# Power.net
KiCad netlist of a schematic drawn in Altium Designer
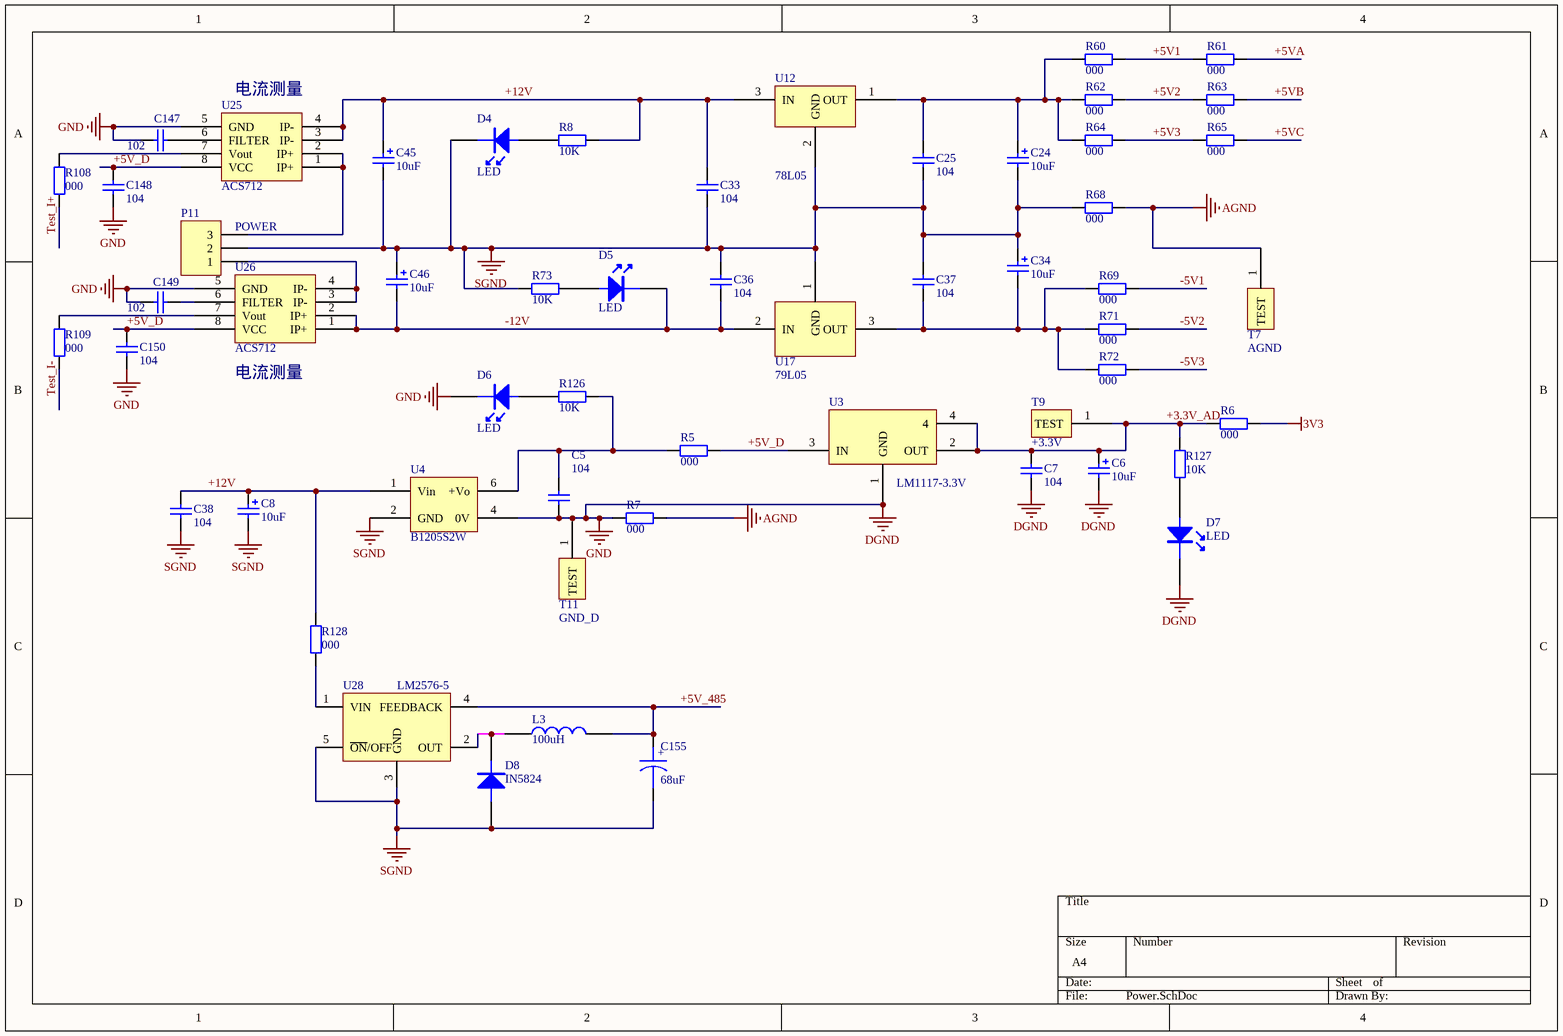
[diagram p0: Power.SchDoc]

(export (version "E")
  (design (tool "Eeschema 10.0.6"))
  (components
    (comp (ref "C5")
      (value "104")
      (footprint "0805C")
      (description "Capacitor")
      (fields (field (name "PUBLISHER") "Altium Limited"))
      (libsource (lib "Miscellaneous Devices") (part "Cap"))
    )
    (comp (ref "C6")
      (value "10uF")
      (footprint "C68uF")
      (description "Polarized Capacitor (Axial)")
      (fields (field (name "PUBLISHER") "Altium Limited"))
      (libsource (lib "Miscellaneous Devices") (part "Cap Pol2"))
    )
    (comp (ref "C7")
      (value "104")
      (footprint "0805C")
      (description "Capacitor")
      (fields (field (name "PUBLISHER") "Altium Limited"))
      (libsource (lib "Miscellaneous Devices") (part "Cap"))
    )
    (comp (ref "C8")
      (value "10uF")
      (footprint "C68uF")
      (description "Polarized Capacitor (Axial)")
      (fields (field (name "PUBLISHER") "Altium Limited"))
      (libsource (lib "Miscellaneous Devices") (part "Cap Pol2"))
    )
    (comp (ref "C24")
      (value "10uF")
      (footprint "C68uF")
      (description "Polarized Capacitor (Axial)")
      (fields (field (name "PUBLISHER") "Altium Limited"))
      (libsource (lib "Miscellaneous Devices") (part "Cap Pol2"))
    )
    (comp (ref "C25")
      (value "104")
      (footprint "0805C")
      (description "Capacitor")
      (fields (field (name "PUBLISHER") "Altium Limited"))
      (libsource (lib "Miscellaneous Devices") (part "Cap"))
    )
    (comp (ref "C33")
      (value "104")
      (footprint "0805C")
      (description "Capacitor")
      (fields (field (name "PUBLISHER") "Altium Limited"))
      (libsource (lib "Miscellaneous Devices") (part "Cap"))
    )
    (comp (ref "C34")
      (value "10uF")
      (footprint "C68uF")
      (description "Polarized Capacitor (Axial)")
      (fields (field (name "PUBLISHER") "Altium Limited"))
      (libsource (lib "Miscellaneous Devices") (part "Cap Pol2"))
    )
    (comp (ref "C36")
      (value "104")
      (footprint "0805C")
      (description "Capacitor")
      (fields (field (name "PUBLISHER") "Altium Limited"))
      (libsource (lib "Miscellaneous Devices") (part "Cap"))
    )
    (comp (ref "C37")
      (value "104")
      (footprint "0805C")
      (description "Capacitor")
      (fields (field (name "PUBLISHER") "Altium Limited"))
      (libsource (lib "Miscellaneous Devices") (part "Cap"))
    )
    (comp (ref "C38")
      (value "104")
      (footprint "0805C")
      (description "Capacitor")
      (fields (field (name "PUBLISHER") "Altium Limited"))
      (libsource (lib "Miscellaneous Devices") (part "Cap"))
    )
    (comp (ref "C45")
      (value "10uF")
      (footprint "C68uF")
      (description "Polarized Capacitor (Axial)")
      (fields (field (name "PUBLISHER") "Altium Limited"))
      (libsource (lib "Miscellaneous Devices") (part "Cap Pol2"))
    )
    (comp (ref "C46")
      (value "10uF")
      (footprint "C68uF")
      (description "Polarized Capacitor (Axial)")
      (fields (field (name "PUBLISHER") "Altium Limited"))
      (libsource (lib "Miscellaneous Devices") (part "Cap Pol2"))
    )
    (comp (ref "C147")
      (value "102")
      (footprint "0603")
      (description "Capacitor")
      (fields (field (name "PUBLISHER") "Altium Limited"))
      (libsource (lib "Miscellaneous Devices") (part "Cap"))
    )
    (comp (ref "C148")
      (value "104")
      (footprint "0603")
      (description "Capacitor")
      (fields (field (name "PUBLISHER") "Altium Limited"))
      (libsource (lib "Miscellaneous Devices") (part "Cap"))
    )
    (comp (ref "C149")
      (value "102")
      (footprint "0603")
      (description "Capacitor")
      (fields (field (name "PUBLISHER") "Altium Limited"))
      (libsource (lib "Miscellaneous Devices") (part "Cap"))
    )
    (comp (ref "C150")
      (value "104")
      (footprint "0603")
      (description "Capacitor")
      (fields (field (name "PUBLISHER") "Altium Limited"))
      (libsource (lib "Miscellaneous Devices") (part "Cap"))
    )
    (comp (ref "C155")
      (value "68uF")
      (footprint "C68uF")
      (description "Capacitor")
      (libsource (lib "*") (part "CAPACITOR POL"))
    )
    (comp (ref "D4") (value "LED") (footprint "0805_LED") (libsource (lib "*") (part "LED")))
    (comp (ref "D5") (value "LED") (footprint "0805_LED") (libsource (lib "*") (part "LED")))
    (comp (ref "D6") (value "LED") (footprint "0805_LED") (libsource (lib "*") (part "LED")))
    (comp (ref "D7") (value "LED") (footprint "0805_LED") (libsource (lib "*") (part "LED")))
    (comp (ref "D8")
      (value "IN5824")
      (footprint "1N5824")
      (description "Diode")
      (libsource (lib "*") (part "DIODE"))
    )
    (comp (ref "L3") (value "100uH") (footprint "L100uH") (libsource (lib "*") (part "INDUCTOR")))
    (comp (ref "P11")
      (value "POWER")
      (footprint "SIP3-5.08mm")
      (description "Header, 3-Pin")
      (fields (field (name "PUBLISHER") "Altium Limited"))
      (libsource (lib "Miscellaneous Connectors") (part "Header 3"))
    )
    (comp (ref "R5")
      (value "000")
      (footprint "0805R")
      (description "Resistor")
      (fields (field (name "PUBLISHER") "Altium Limited"))
      (libsource (lib "Miscellaneous Devices") (part "Res2"))
    )
    (comp (ref "R6")
      (value "000")
      (footprint "0805R")
      (description "Resistor")
      (fields (field (name "PUBLISHER") "Altium Limited"))
      (libsource (lib "Miscellaneous Devices") (part "Res2"))
    )
    (comp (ref "R7")
      (value "000")
      (footprint "0805R")
      (description "Resistor")
      (fields (field (name "PUBLISHER") "Altium Limited"))
      (libsource (lib "Miscellaneous Devices") (part "Res2"))
    )
    (comp (ref "R8")
      (value "10K")
      (footprint "0603")
      (description "Resistor")
      (fields (field (name "Comment") "Res2") (field (name "PUBLISHER") "Altium Limited"))
      (libsource (lib "") (part "Res2_2"))
    )
    (comp (ref "R60")
      (value "000")
      (footprint "0805R")
      (description "Resistor")
      (fields (field (name "PUBLISHER") "Altium Limited"))
      (libsource (lib "Miscellaneous Devices") (part "Res2"))
    )
    (comp (ref "R61")
      (value "000")
      (footprint "0805R")
      (description "Resistor")
      (fields (field (name "PUBLISHER") "Altium Limited"))
      (libsource (lib "Miscellaneous Devices") (part "Res2"))
    )
    (comp (ref "R62")
      (value "000")
      (footprint "0805R")
      (description "Resistor")
      (fields (field (name "PUBLISHER") "Altium Limited"))
      (libsource (lib "Miscellaneous Devices") (part "Res2"))
    )
    (comp (ref "R63")
      (value "000")
      (footprint "0805R")
      (description "Resistor")
      (fields (field (name "PUBLISHER") "Altium Limited"))
      (libsource (lib "Miscellaneous Devices") (part "Res2"))
    )
    (comp (ref "R64")
      (value "000")
      (footprint "0805R")
      (description "Resistor")
      (fields (field (name "PUBLISHER") "Altium Limited"))
      (libsource (lib "Miscellaneous Devices") (part "Res2"))
    )
    (comp (ref "R65")
      (value "000")
      (footprint "0805R")
      (description "Resistor")
      (fields (field (name "PUBLISHER") "Altium Limited"))
      (libsource (lib "Miscellaneous Devices") (part "Res2"))
    )
    (comp (ref "R68")
      (value "000")
      (footprint "0805R")
      (description "Resistor")
      (fields (field (name "PUBLISHER") "Altium Limited"))
      (libsource (lib "Miscellaneous Devices") (part "Res2"))
    )
    (comp (ref "R69")
      (value "000")
      (footprint "0805R")
      (description "Resistor")
      (fields (field (name "PUBLISHER") "Altium Limited"))
      (libsource (lib "Miscellaneous Devices") (part "Res2"))
    )
    (comp (ref "R71")
      (value "000")
      (footprint "0805R")
      (description "Resistor")
      (fields (field (name "PUBLISHER") "Altium Limited"))
      (libsource (lib "Miscellaneous Devices") (part "Res2"))
    )
    (comp (ref "R72")
      (value "000")
      (footprint "0805R")
      (description "Resistor")
      (fields (field (name "PUBLISHER") "Altium Limited"))
      (libsource (lib "Miscellaneous Devices") (part "Res2"))
    )
    (comp (ref "R73")
      (value "10K")
      (footprint "0603")
      (description "Resistor")
      (fields (field (name "Comment") "Res2") (field (name "PUBLISHER") "Altium Limited"))
      (libsource (lib "Miscellaneous Devices") (part "Res2"))
    )
    (comp (ref "R108")
      (value "000")
      (footprint "0603")
      (description "Resistor")
      (fields (field (name "PUBLISHER") "Altium Limited"))
      (libsource (lib "") (part "Res2_1"))
    )
    (comp (ref "R109")
      (value "000")
      (footprint "0603")
      (description "Resistor")
      (fields (field (name "PUBLISHER") "Altium Limited"))
      (libsource (lib "") (part "Res2_1"))
    )
    (comp (ref "R126")
      (value "10K")
      (footprint "0603")
      (description "Resistor")
      (fields (field (name "Comment") "Res2") (field (name "PUBLISHER") "Altium Limited"))
      (libsource (lib "") (part "Res2_2"))
    )
    (comp (ref "R127")
      (value "10K")
      (footprint "0603")
      (description "Resistor")
      (fields (field (name "Comment") "Res2") (field (name "PUBLISHER") "Altium Limited"))
      (libsource (lib "") (part "Res2_1"))
    )
    (comp (ref "R128")
      (value "000")
      (footprint "0805R")
      (description "Resistor")
      (fields (field (name "PUBLISHER") "Altium Limited"))
      (libsource (lib "") (part "Res2_3"))
    )
    (comp (ref "T7") (value "AGND") (footprint "TEST") (libsource (lib "Schlib1") (part "TEST")))
    (comp (ref "T9") (value "+3.3V") (footprint "TEST") (libsource (lib "") (part "TEST_1")))
    (comp (ref "T11") (value "GND_D") (footprint "TEST") (libsource (lib "Schlib1") (part "TEST")))
    (comp (ref "U3")
      (value "LM1117-3.3V")
      (footprint "SOT223")
      (libsource (lib "Schlib1") (part "LM1117-3.3V"))
    )
    (comp (ref "U4") (value "B1205S2W") (footprint "B1205SW") (libsource (lib "Schlib1") (part "B1205S2W")))
    (comp (ref "U12") (value "78L05") (footprint "SOT89-M") (libsource (lib "Schlib1") (part "78L05")))
    (comp (ref "U17") (value "79L05") (libsource (lib "Schlib1") (part "79L05")))
    (comp (ref "U25") (value "ACS712") (footprint "SO8") (libsource (lib "Schlib1") (part "ACS712")))
    (comp (ref "U26") (value "ACS712") (footprint "SO8") (libsource (lib "Schlib1") (part "ACS712")))
    (comp (ref "U28") (value "LM2576-5") (footprint "lm2596") (libsource (lib "*") (part "LM2596-5")))
  )
  (nets
    (net (code "1") (name "/+3.3V_AD") (class "Default")
      (node (ref "C6") (pin "1") (pinfunction "1_1") (pintype "passive"))
      (node (ref "C7") (pin "1") (pinfunction "1_1") (pintype "passive"))
      (node (ref "R127") (pin "2") (pinfunction "2_2") (pintype "passive"))
      (node (ref "R6") (pin "2") (pinfunction "2_2") (pintype "passive"))
      (node (ref "T9") (pin "1") (pinfunction "TEST_1") (pintype "passive"))
      (node (ref "U3") (pin "2") (pinfunction "OUT_2") (pintype "passive"))
      (node (ref "U3") (pin "4") (pinfunction "4_4") (pintype "passive"))
    )
    (net (code "2") (name "/+5V1") (class "Default")
      (node (ref "R60") (pin "1") (pinfunction "1_1") (pintype "passive"))
      (node (ref "R61") (pin "2") (pinfunction "2_2") (pintype "passive"))
    )
    (net (code "3") (name "/+5V2") (class "Default")
      (node (ref "R62") (pin "1") (pinfunction "1_1") (pintype "passive"))
      (node (ref "R63") (pin "2") (pinfunction "2_2") (pintype "passive"))
    )
    (net (code "4") (name "/+5V3") (class "Default")
      (node (ref "R64") (pin "1") (pinfunction "1_1") (pintype "passive"))
      (node (ref "R65") (pin "2") (pinfunction "2_2") (pintype "passive"))
    )
    (net (code "5") (name "/+5VA") (class "Default")
      (node (ref "R61") (pin "1") (pinfunction "1_1") (pintype "passive"))
    )
    (net (code "6") (name "/+5VB") (class "Default")
      (node (ref "R63") (pin "1") (pinfunction "1_1") (pintype "passive"))
    )
    (net (code "7") (name "/+5VC") (class "Default")
      (node (ref "R65") (pin "1") (pinfunction "1_1") (pintype "passive"))
    )
    (net (code "8") (name "/+5V_485") (class "Default")
      (node (ref "C155") (pin "1") (pinfunction "1_1") (pintype "passive"))
      (node (ref "L3") (pin "2") (pinfunction "2_2") (pintype "passive"))
      (node (ref "U28") (pin "4") (pinfunction "FEEDBACK_4") (pintype "passive"))
    )
    (net (code "9") (name "/+5V_D") (class "Default")
      (node (ref "C148") (pin "1") (pinfunction "1_1") (pintype "passive"))
      (node (ref "C150") (pin "1") (pinfunction "1_1") (pintype "passive"))
      (node (ref "R5") (pin "1") (pinfunction "1_1") (pintype "passive"))
      (node (ref "U25") (pin "8") (pinfunction "VCC_8") (pintype "passive"))
      (node (ref "U26") (pin "8") (pinfunction "VCC_8") (pintype "passive"))
      (node (ref "U3") (pin "3") (pinfunction "IN_3") (pintype "passive"))
    )
    (net (code "10") (name "/+12V") (class "Default")
      (node (ref "C33") (pin "1") (pinfunction "1_1") (pintype "passive"))
      (node (ref "C38") (pin "1") (pinfunction "1_1") (pintype "passive"))
      (node (ref "C45") (pin "1") (pinfunction "1_1") (pintype "passive"))
      (node (ref "C8") (pin "1") (pinfunction "1_1") (pintype "passive"))
      (node (ref "R128") (pin "1") (pinfunction "1_1") (pintype "passive"))
      (node (ref "R8") (pin "2") (pinfunction "2_2") (pintype "passive"))
      (node (ref "U12") (pin "3") (pinfunction "IN_3") (pintype "passive"))
      (node (ref "U25") (pin "3") (pinfunction "IP-_3") (pintype "passive"))
      (node (ref "U25") (pin "4") (pinfunction "IP-_4") (pintype "passive"))
      (node (ref "U4") (pin "1") (pinfunction "Vin_1") (pintype "passive"))
    )
    (net (code "11") (name "/-5V1") (class "Default")
      (node (ref "R69") (pin "1") (pinfunction "1_1") (pintype "passive"))
    )
    (net (code "12") (name "/-5V2") (class "Default")
      (node (ref "R71") (pin "1") (pinfunction "1_1") (pintype "passive"))
    )
    (net (code "13") (name "/-5V3") (class "Default")
      (node (ref "R72") (pin "1") (pinfunction "1_1") (pintype "passive"))
    )
    (net (code "14") (name "/-12V") (class "Default")
      (node (ref "C36") (pin "2") (pinfunction "2_2") (pintype "passive"))
      (node (ref "C46") (pin "2") (pinfunction "2_2") (pintype "passive"))
      (node (ref "D5") (pin "2") (pinfunction "K_2") (pintype "passive"))
      (node (ref "U17") (pin "2") (pinfunction "IN_2") (pintype "passive"))
      (node (ref "U26") (pin "1") (pinfunction "IP+_1") (pintype "passive"))
      (node (ref "U26") (pin "2") (pinfunction "IP+_2") (pintype "passive"))
    )
    (net (code "15") (name "/Test_I+") (class "Default")
      (node (ref "R108") (pin "1") (pinfunction "1_1") (pintype "passive"))
    )
    (net (code "16") (name "/Test_I-") (class "Default")
      (node (ref "R109") (pin "1") (pinfunction "1_1") (pintype "passive"))
    )
    (net (code "17") (name "3V3") (class "Default")
      (node (ref "R6") (pin "1") (pinfunction "1_1") (pintype "passive"))
    )
    (net (code "18") (name "AGND") (class "Default")
      (node (ref "R68") (pin "1") (pinfunction "1_1") (pintype "passive"))
      (node (ref "R7") (pin "1") (pinfunction "1_1") (pintype "passive"))
      (node (ref "T7") (pin "1") (pinfunction "TEST_1") (pintype "passive"))
    )
    (net (code "19") (name "DGND") (class "Default")
      (node (ref "C147") (pin "1") (pinfunction "1_1") (pintype "passive"))
      (node (ref "C148") (pin "2") (pinfunction "2_2") (pintype "passive"))
      (node (ref "C149") (pin "1") (pinfunction "1_1") (pintype "passive"))
      (node (ref "C150") (pin "2") (pinfunction "2_2") (pintype "passive"))
      (node (ref "C5") (pin "2") (pinfunction "2_2") (pintype "passive"))
      (node (ref "C6") (pin "2") (pinfunction "2_2") (pintype "passive"))
      (node (ref "C7") (pin "2") (pinfunction "2_2") (pintype "passive"))
      (node (ref "D6") (pin "2") (pinfunction "K_2") (pintype "passive"))
      (node (ref "D7") (pin "2") (pinfunction "K_2") (pintype "passive"))
      (node (ref "R7") (pin "2") (pinfunction "2_2") (pintype "passive"))
      (node (ref "T11") (pin "1") (pinfunction "TEST_1") (pintype "passive"))
      (node (ref "U25") (pin "5") (pinfunction "GND_5") (pintype "passive"))
      (node (ref "U26") (pin "5") (pinfunction "GND_5") (pintype "passive"))
      (node (ref "U3") (pin "1") (pinfunction "GND_1") (pintype "passive"))
      (node (ref "U4") (pin "4") (pinfunction "0V_4") (pintype "passive"))
    )
    (net (code "20") (name "Net-(D4-A)") (class "Default")
      (node (ref "D4") (pin "1") (pinfunction "A_1") (pintype "passive"))
      (node (ref "R8") (pin "1") (pinfunction "1_1") (pintype "passive"))
    )
    (net (code "21") (name "Net-(D5-A)") (class "Default")
      (node (ref "D5") (pin "1") (pinfunction "A_1") (pintype "passive"))
      (node (ref "R73") (pin "1") (pinfunction "1_1") (pintype "passive"))
    )
    (net (code "22") (name "Net-(D6-A)") (class "Default")
      (node (ref "D6") (pin "1") (pinfunction "A_1") (pintype "passive"))
      (node (ref "R126") (pin "1") (pinfunction "1_1") (pintype "passive"))
    )
    (net (code "23") (name "Net-(D7-A)") (class "Default")
      (node (ref "D7") (pin "1") (pinfunction "A_1") (pintype "passive"))
      (node (ref "R127") (pin "1") (pinfunction "1_1") (pintype "passive"))
    )
    (net (code "24") (name "Net-(D8-K)") (class "Default")
      (node (ref "D8") (pin "2") (pinfunction "K_2") (pintype "passive"))
      (node (ref "L3") (pin "1") (pinfunction "1_1") (pintype "passive"))
      (node (ref "U28") (pin "2") (pinfunction "OUT_2") (pintype "passive"))
    )
    (net (code "25") (name "Net-(P11-Pad1)") (class "Default")
      (node (ref "P11") (pin "1") (pinfunction "1_1") (pintype "passive"))
      (node (ref "U26") (pin "3") (pinfunction "IP-_3") (pintype "passive"))
      (node (ref "U26") (pin "4") (pinfunction "IP-_4") (pintype "passive"))
    )
    (net (code "26") (name "Net-(P11-Pad3)") (class "Default")
      (node (ref "P11") (pin "3") (pinfunction "3_3") (pintype "passive"))
      (node (ref "U25") (pin "1") (pinfunction "IP+_1") (pintype "passive"))
      (node (ref "U25") (pin "2") (pinfunction "IP+_2") (pintype "passive"))
    )
    (net (code "27") (name "Net-(U4-+Vo)") (class "Default")
      (node (ref "C5") (pin "1") (pinfunction "1_1") (pintype "passive"))
      (node (ref "R126") (pin "2") (pinfunction "2_2") (pintype "passive"))
      (node (ref "R5") (pin "2") (pinfunction "2_2") (pintype "passive"))
      (node (ref "U4") (pin "6") (pinfunction "+Vo_6") (pintype "passive"))
    )
    (net (code "28") (name "Net-(U12-OUT)") (class "Default")
      (node (ref "C24") (pin "1") (pinfunction "1_1") (pintype "passive"))
      (node (ref "C25") (pin "1") (pinfunction "1_1") (pintype "passive"))
      (node (ref "R60") (pin "2") (pinfunction "2_2") (pintype "passive"))
      (node (ref "R62") (pin "2") (pinfunction "2_2") (pintype "passive"))
      (node (ref "R64") (pin "2") (pinfunction "2_2") (pintype "passive"))
      (node (ref "U12") (pin "1") (pinfunction "OUT_1") (pintype "passive"))
    )
    (net (code "29") (name "Net-(U17-OUT)") (class "Default")
      (node (ref "C34") (pin "2") (pinfunction "2_2") (pintype "passive"))
      (node (ref "C37") (pin "2") (pinfunction "2_2") (pintype "passive"))
      (node (ref "R69") (pin "2") (pinfunction "2_2") (pintype "passive"))
      (node (ref "R71") (pin "2") (pinfunction "2_2") (pintype "passive"))
      (node (ref "R72") (pin "2") (pinfunction "2_2") (pintype "passive"))
      (node (ref "U17") (pin "3") (pinfunction "OUT_3") (pintype "passive"))
    )
    (net (code "30") (name "Net-(U25-FILTER)") (class "Default")
      (node (ref "C147") (pin "2") (pinfunction "2_2") (pintype "passive"))
      (node (ref "U25") (pin "6") (pinfunction "FILTER_6") (pintype "passive"))
    )
    (net (code "31") (name "Net-(U25-Vout)") (class "Default")
      (node (ref "R108") (pin "2") (pinfunction "2_2") (pintype "passive"))
      (node (ref "U25") (pin "7") (pinfunction "Vout_7") (pintype "passive"))
    )
    (net (code "32") (name "Net-(U26-FILTER)") (class "Default")
      (node (ref "C149") (pin "2") (pinfunction "2_2") (pintype "passive"))
      (node (ref "U26") (pin "6") (pinfunction "FILTER_6") (pintype "passive"))
    )
    (net (code "33") (name "Net-(U26-Vout)") (class "Default")
      (node (ref "R109") (pin "2") (pinfunction "2_2") (pintype "passive"))
      (node (ref "U26") (pin "7") (pinfunction "Vout_7") (pintype "passive"))
    )
    (net (code "34") (name "Net-(U28-VIN)") (class "Default")
      (node (ref "R128") (pin "2") (pinfunction "2_2") (pintype "passive"))
      (node (ref "U28") (pin "1") (pinfunction "VIN_1") (pintype "passive"))
    )
    (net (code "35") (name "SGND") (class "Default")
      (node (ref "C155") (pin "2") (pinfunction "2_2") (pintype "passive"))
      (node (ref "C24") (pin "2") (pinfunction "2_2") (pintype "passive"))
      (node (ref "C25") (pin "2") (pinfunction "2_2") (pintype "passive"))
      (node (ref "C33") (pin "2") (pinfunction "2_2") (pintype "passive"))
      (node (ref "C34") (pin "1") (pinfunction "1_1") (pintype "passive"))
      (node (ref "C36") (pin "1") (pinfunction "1_1") (pintype "passive"))
      (node (ref "C37") (pin "1") (pinfunction "1_1") (pintype "passive"))
      (node (ref "C38") (pin "2") (pinfunction "2_2") (pintype "passive"))
      (node (ref "C45") (pin "2") (pinfunction "2_2") (pintype "passive"))
      (node (ref "C46") (pin "1") (pinfunction "1_1") (pintype "passive"))
      (node (ref "C8") (pin "2") (pinfunction "2_2") (pintype "passive"))
      (node (ref "D4") (pin "2") (pinfunction "K_2") (pintype "passive"))
      (node (ref "D8") (pin "1") (pinfunction "A_1") (pintype "passive"))
      (node (ref "P11") (pin "2") (pinfunction "2_2") (pintype "passive"))
      (node (ref "R68") (pin "2") (pinfunction "2_2") (pintype "passive"))
      (node (ref "R73") (pin "2") (pinfunction "2_2") (pintype "passive"))
      (node (ref "U12") (pin "2") (pinfunction "GND_2") (pintype "passive"))
      (node (ref "U17") (pin "1") (pinfunction "GND_1") (pintype "passive"))
      (node (ref "U28") (pin "3") (pinfunction "GND_3") (pintype "passive"))
      (node (ref "U28") (pin "5") (pinfunction "~{ON}/OFF_5") (pintype "passive"))
      (node (ref "U4") (pin "2") (pinfunction "GND_2") (pintype "passive"))
    )
  )
)
